# 40106-4069-Synth.net
KiCad netlist of a schematic drawn in EAGLE
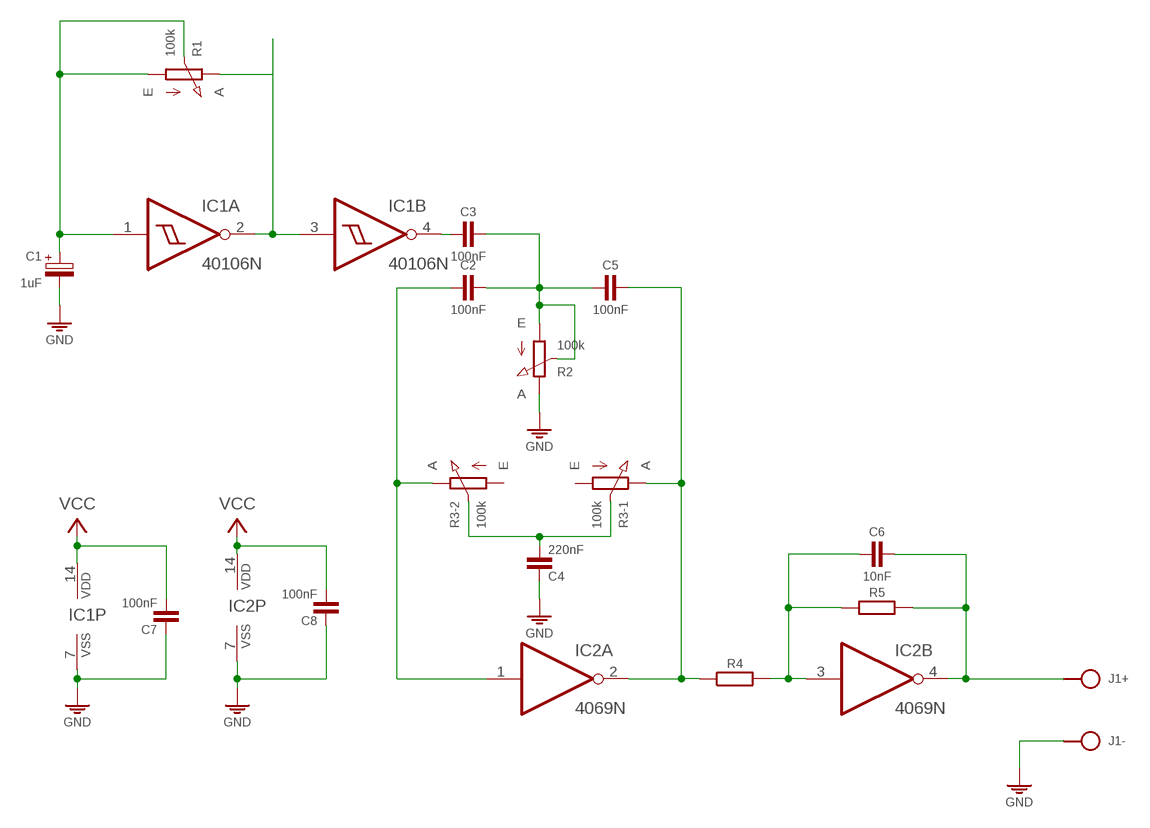
[diagram p0: schematic, sheet 1]

(export (version "E")
  (design (tool "Eeschema 10.0.6"))
  (components
    (comp (ref "C1")
      (value "1uF")
      (footprint "eagle-import:E2.5-4_V")
      (libsource (lib "eagle-import") (part "CPOLE2,5-4/V"))
    )
    (comp (ref "C2")
      (value "100nF")
      (footprint "eagle-import:C050-020X044")
      (libsource (lib "eagle-import") (part "C-H050-020X044"))
    )
    (comp (ref "C3")
      (value "100nF")
      (footprint "eagle-import:C050-020X044")
      (libsource (lib "eagle-import") (part "C-H050-020X044"))
    )
    (comp (ref "C4")
      (value "220nF")
      (footprint "eagle-import:C050-020X044_V")
      (libsource (lib "eagle-import") (part "C050-020X044/V"))
    )
    (comp (ref "C5")
      (value "100nF")
      (footprint "eagle-import:C050-020X044")
      (libsource (lib "eagle-import") (part "C-H050-020X044"))
    )
    (comp (ref "C6")
      (value "10nF")
      (footprint "eagle-import:C050-020X044")
      (libsource (lib "eagle-import") (part "C-H050-020X044"))
    )
    (comp (ref "C7")
      (value "100nF")
      (footprint "eagle-import:C050-020X044_V")
      (libsource (lib "eagle-import") (part "C050-020X044/V"))
    )
    (comp (ref "C8")
      (value "100nF")
      (footprint "eagle-import:C050-020X044_V")
      (libsource (lib "eagle-import") (part "C050-020X044/V"))
    )
    (comp (ref "IC1")
      (value "40106N")
      (footprint "eagle-import:DIL14")
      (libsource (lib "eagle-import") (part "40106N"))
    )
    (comp (ref "IC2")
      (value "4069N")
      (footprint "eagle-import:DIL14")
      (libsource (lib "eagle-import") (part "4069N"))
    )
    (comp (ref "J1")
      (value "SPAD+-+-")
      (footprint "eagle-import:SPAD+-")
      (libsource (lib "eagle-import") (part "SPAD+-+-"))
    )
    (comp (ref "J2")
      (value "VCC_GNDL")
      (footprint "eagle-import:SPAD-+")
      (libsource (lib "eagle-import") (part "VCC_GNDL"))
    )
    (comp (ref "R1")
      (value "100k")
      (footprint "eagle-import:POT")
      (libsource (lib "eagle-import") (part "POT"))
    )
    (comp (ref "R2")
      (value "100k")
      (footprint "eagle-import:POT")
      (libsource (lib "eagle-import") (part "POT"))
    )
    (comp (ref "R3")
      (value "100k")
      (footprint "eagle-import:POT-STEREO-2X3")
      (libsource (lib "eagle-import") (part "POT-STEREO"))
    )
    (comp (ref "R4")
      (value "R-H0204/2-V")
      (footprint "eagle-import:0204V")
      (libsource (lib "eagle-import") (part "R-H0204/2-V"))
    )
    (comp (ref "R5")
      (value "R-H0204/10-V")
      (footprint "eagle-import:0204_10-V")
      (libsource (lib "eagle-import") (part "R-H0204/10-V"))
    )
  )
  (nets
    (net (code "1") (name "GND") (class "Default")
      (node (ref "C1") (pin "-") (pinfunction "-_-") (pintype "passive"))
      (node (ref "C4") (pin "1") (pinfunction "1_1") (pintype "passive"))
      (node (ref "C7") (pin "1") (pinfunction "1_1") (pintype "passive"))
      (node (ref "C8") (pin "1") (pinfunction "1_1") (pintype "passive"))
      (node (ref "IC1") (pin "7") (pinfunction "VSS_7") (pintype "power_in"))
      (node (ref "IC2") (pin "7") (pinfunction "VSS_7") (pintype "power_in"))
      (node (ref "J1") (pin "1") (pinfunction "P$1_1") (pintype "passive"))
      (node (ref "J2") (pin "1") (pinfunction "GND_1") (pintype "power_in"))
      (node (ref "R2") (pin "3") (pinfunction "E_3") (pintype "passive"))
    )
    (net (code "2") (name "Net-(IC1A-I)") (class "Default")
      (node (ref "C1") (pin "+") (pinfunction "+_+") (pintype "passive"))
      (node (ref "IC1") (pin "1") (pinfunction "I_1") (pintype "input"))
      (node (ref "R1") (pin "1") (pinfunction "A_1") (pintype "passive"))
      (node (ref "R1") (pin "2") (pinfunction "S_2") (pintype "passive"))
    )
    (net (code "3") (name "Net-(IC1A-O)") (class "Default")
      (node (ref "IC1") (pin "2") (pinfunction "O_2") (pintype "output"))
      (node (ref "IC1") (pin "3") (pinfunction "I_3") (pintype "input"))
      (node (ref "R1") (pin "3") (pinfunction "E_3") (pintype "passive"))
    )
    (net (code "4") (name "Net-(IC1B-O)") (class "Default")
      (node (ref "C3") (pin "1") (pinfunction "1_1") (pintype "passive"))
      (node (ref "IC1") (pin "4") (pinfunction "O_4") (pintype "output"))
    )
    (net (code "5") (name "Net-(IC2A-I)") (class "Default")
      (node (ref "C2") (pin "1") (pinfunction "1_1") (pintype "passive"))
      (node (ref "IC2") (pin "1") (pinfunction "I_1") (pintype "input"))
      (node (ref "R3") (pin "2-E") (pinfunction "E_2-E") (pintype "passive"))
    )
    (net (code "6") (name "Net-(IC2A-O)") (class "Default")
      (node (ref "C5") (pin "2") (pinfunction "2_2") (pintype "passive"))
      (node (ref "IC2") (pin "2") (pinfunction "O_2") (pintype "output"))
      (node (ref "R3") (pin "1-E") (pinfunction "E_1-E") (pintype "passive"))
      (node (ref "R4") (pin "1") (pinfunction "1_1") (pintype "passive"))
    )
    (net (code "7") (name "Net-(IC2B-I)") (class "Default")
      (node (ref "C6") (pin "1") (pinfunction "1_1") (pintype "passive"))
      (node (ref "IC2") (pin "3") (pinfunction "I_3") (pintype "input"))
      (node (ref "R4") (pin "2") (pinfunction "2_2") (pintype "passive"))
      (node (ref "R5") (pin "1") (pinfunction "1_1") (pintype "passive"))
    )
    (net (code "8") (name "Net-(IC2B-O)") (class "Default")
      (node (ref "C6") (pin "2") (pinfunction "2_2") (pintype "passive"))
      (node (ref "IC2") (pin "4") (pinfunction "O_4") (pintype "output"))
      (node (ref "J1") (pin "2") (pinfunction "P$1_2") (pintype "passive"))
      (node (ref "R5") (pin "2") (pinfunction "2_2") (pintype "passive"))
    )
    (net (code "9") (name "Net-(R2-A)") (class "Default")
      (node (ref "C2") (pin "2") (pinfunction "2_2") (pintype "passive"))
      (node (ref "C3") (pin "2") (pinfunction "2_2") (pintype "passive"))
      (node (ref "C5") (pin "1") (pinfunction "1_1") (pintype "passive"))
      (node (ref "R2") (pin "1") (pinfunction "A_1") (pintype "passive"))
      (node (ref "R2") (pin "2") (pinfunction "S_2") (pintype "passive"))
    )
    (net (code "10") (name "Net-(R3A-S)") (class "Default")
      (node (ref "C4") (pin "2") (pinfunction "2_2") (pintype "passive"))
      (node (ref "R3") (pin "1-S") (pinfunction "S_1-S") (pintype "passive"))
      (node (ref "R3") (pin "2-S") (pinfunction "S_2-S") (pintype "passive"))
    )
    (net (code "11") (name "VCC") (class "Default")
      (node (ref "C7") (pin "2") (pinfunction "2_2") (pintype "passive"))
      (node (ref "C8") (pin "2") (pinfunction "2_2") (pintype "passive"))
      (node (ref "IC1") (pin "14") (pinfunction "VDD_14") (pintype "power_in"))
      (node (ref "IC2") (pin "14") (pinfunction "VDD_14") (pintype "power_in"))
      (node (ref "J2") (pin "2") (pinfunction "VCC_2") (pintype "power_in"))
    )
    (net (code "12") (name "unconnected-(R3A-A-Pad1-A)") (class "Default")
      (node (ref "R3") (pin "1-A") (pinfunction "A_1-A") (pintype "passive"))
    )
    (net (code "13") (name "unconnected-(R3B-A-Pad2-A)") (class "Default")
      (node (ref "R3") (pin "2-A") (pinfunction "A_2-A") (pintype "passive"))
    )
  )
)
